# Seperation_Switches.net
KiCad netlist of a schematic drawn in Altium Designer
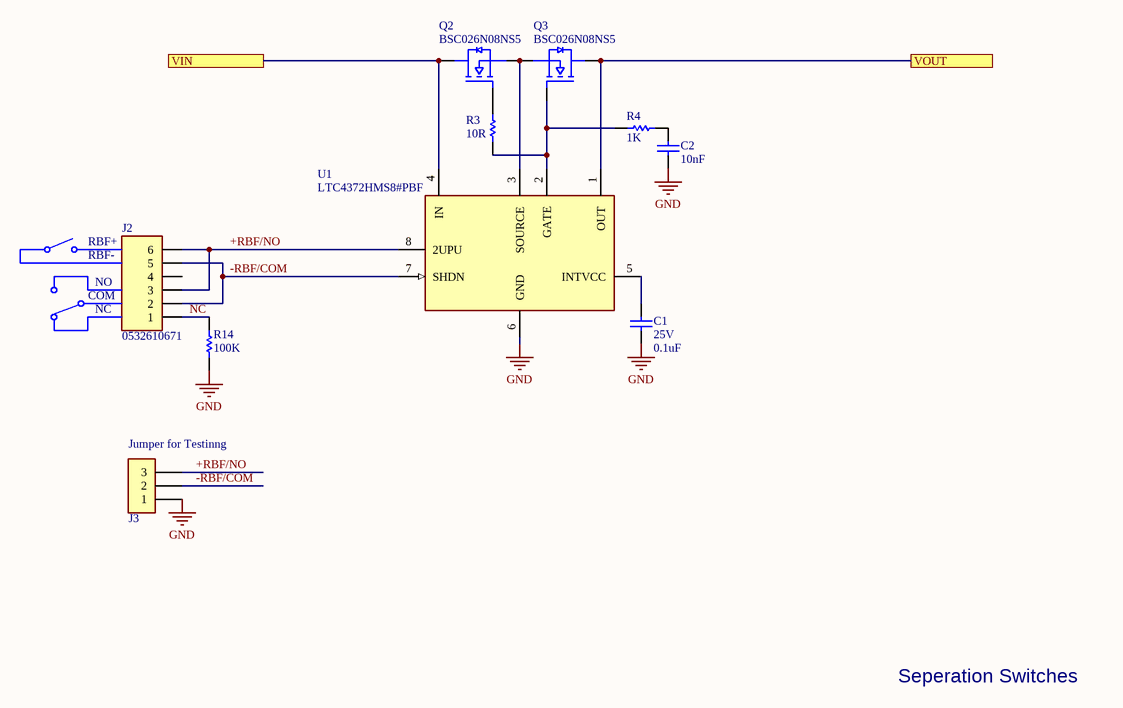
[diagram p0: Seperation_Switches.SchDoc]

(export (version "E")
  (design (tool "Eeschema 10.0.6"))
  (components
    (comp (ref "C1")
      (value "CL21B104KACNNNC")
      (footprint "CAPC0805X060")
      (description "0.1uF ±10% 25V Ceramic Capacitor X7R 0805 (2012 Metric)")
      (fields
        (field (name "DISTRIBUTOR PART NUMBER") "1276-1099-1-ND")
        (field (name "TOLERANCE") "10%")
        (field (name "VOLTAGE RATING") "25V")
        (field (name "CAPACITANCE") "0.1uF")
      )
      (libsource (lib "Ahristi_Library") (part "CL21B104KACNNNC"))
    )
    (comp (ref "C2")
      (value "CL21B103KBANNNC")
      (footprint "CAPC0805X060")
      (description "10nF ±10% 50V Ceramic Capacitor X7R 0805 (2012 Metric)")
      (fields
        (field (name "DISTRIBUTOR PART NUMBER") "1276-1015-1-ND")
        (field (name "TOLERANCE") "10%")
        (field (name "CAPACITANCE") "10nF")
      )
      (libsource (lib "Ahristi_Library") (part "CL21B103KBANNNC"))
    )
    (comp (ref "J2")
      (value "0532610671")
      (footprint "0532610671")
      (description "Connector Header Surface Mount, Right Angle 6 position 0.049\" (1.25mm) Picoblade")
      (fields (field (name "DISTRIBUTOR PART NUMBER") "WM7624CT-ND"))
      (libsource (lib "Ahristi_Library") (part "0532610671"))
    )
    (comp (ref "J3")
      (value "61300311121")
      (footprint "61300311121")
      (description "Header 2.54mm, 1x3 Position")
      (fields (field (name "DISTRIBUTOR PART NUMBER") "732-5316-ND"))
      (libsource (lib "Ahristi_Library") (part "61300311121"))
    )
    (comp (ref "Q2")
      (value "BSC026N08NS5")
      (footprint "PG-TDSON-8-5")
      (description "80V N-Channel 23A (Ta), 100A (Tc) 2.5W (Ta), 156W (Tc) Surface Mount PG-TDSON-8-6")
      (fields (field (name "DISTRIBUTOR PART NUMBER") "BSC026N08NS5ATMA1CT-ND"))
      (libsource (lib "Ahristi_Library") (part "BSC026N08NS5"))
    )
    (comp (ref "Q3")
      (value "BSC026N08NS5")
      (footprint "PG-TDSON-8-5")
      (description "80V N-Channel 23A (Ta), 100A (Tc) 2.5W (Ta), 156W (Tc) Surface Mount PG-TDSON-8-6")
      (fields (field (name "DISTRIBUTOR PART NUMBER") "BSC026N08NS5ATMA1CT-ND"))
      (libsource (lib "Ahristi_Library") (part "BSC026N08NS5"))
    )
    (comp (ref "R3")
      (value "RMCF0603FT10R0")
      (footprint "RESC0603")
      (description "10 Ohms ±1% 0.1W, 1/10W Chip Resistor 0603 (1608 Metric) Automotive AEC-Q200 Thick Film")
      (fields
        (field (name "TOLERANCE") "1%")
        (field (name "DISTRIBUTOR PART NUMBER") "RMCF0603FT10R0CT-ND")
        (field (name "RESISTANCE") "10R")
      )
      (libsource (lib "Ahristi_Library") (part "RMCF0603FT10R0"))
    )
    (comp (ref "R4")
      (value "RNCP0805FTD1K00")
      (footprint "RESC0805")
      (description "1 kOhms ±1% 0.25W, 1/4W Chip Resistor 0805 (2012 Metric) Anti-Sulfur Thin Film")
      (fields
        (field (name "TOLERANCE") "1%")
        (field (name "DISTRIBUTOR PART NUMBER") "RNCP0805FTD1K00CT-ND")
        (field (name "RESISTANCE") "1K")
      )
      (libsource (lib "Ahristi_Library") (part "RNCP0805FTD1K00"))
    )
    (comp (ref "R14")
      (value "RMCF0603FT100K")
      (footprint "RESC0603")
      (description "100 kOhms ±1% 0.1W, 1/10W Chip Resistor 0603 (1608 Metric) Automotive AEC-Q200 Thick Film")
      (fields
        (field (name "TOLERANCE") "1%")
        (field (name "DISTRIBUTOR PART NUMBER") "RMCF0603FT100KCT-ND")
        (field (name "RESISTANCE") "100K")
      )
      (libsource (lib "Ahristi_Library") (part "RMCF0603FT100K"))
    )
    (comp (ref "U1")
      (value "LTC4372HMS8#PBF")
      (footprint "MS8-8LEAD")
      (description "Ideal Diode Controller, 8-lead MSOP SHDN")
      (fields
        (field (name "DISTRIBUTOR PART NUMBER") "505-LTC4372HMS8#PBF-ND")
        (field (name "MANUFACTURER PART NUMBER") "LTC4373CMS8#PBF")
      )
      (libsource (lib "Ahristi_Library") (part "LTC4372HMS8#PBF"))
    )
  )
  (nets
    (net (code "1") (name "/+RBF{slash}NO") (class "Default")
      (node (ref "J2") (pin "3") (pinfunction "3_3") (pintype "passive"))
      (node (ref "J2") (pin "6") (pinfunction "6_6") (pintype "passive"))
      (node (ref "J3") (pin "3") (pinfunction "3_3") (pintype "passive"))
      (node (ref "U1") (pin "8") (pinfunction "2UPU_8") (pintype "passive"))
    )
    (net (code "2") (name "/-RBF{slash}COM") (class "Default")
      (node (ref "J2") (pin "2") (pinfunction "2_2") (pintype "passive"))
      (node (ref "J2") (pin "5") (pinfunction "5_5") (pintype "passive"))
      (node (ref "J3") (pin "2") (pinfunction "2_2") (pintype "passive"))
      (node (ref "U1") (pin "7") (pinfunction "SHDN_7") (pintype "input"))
    )
    (net (code "3") (name "/NC") (class "Default")
      (node (ref "J2") (pin "1") (pinfunction "1_1") (pintype "passive"))
      (node (ref "R14") (pin "2") (pinfunction "2_2") (pintype "passive"))
    )
    (net (code "4") (name "/VIN") (class "Default")
      (node (ref "Q2") (pin "D") (pinfunction "D_D") (pintype "passive"))
      (node (ref "U1") (pin "4") (pinfunction "IN_4") (pintype "passive"))
    )
    (net (code "5") (name "/VOUT") (class "Default")
      (node (ref "Q3") (pin "D") (pinfunction "D_D") (pintype "passive"))
      (node (ref "U1") (pin "1") (pinfunction "OUT_1") (pintype "passive"))
    )
    (net (code "6") (name "GND") (class "Default")
      (node (ref "C1") (pin "1") (pinfunction "1_1") (pintype "passive"))
      (node (ref "C2") (pin "1") (pinfunction "1_1") (pintype "passive"))
      (node (ref "J3") (pin "1") (pinfunction "1_1") (pintype "passive"))
      (node (ref "R14") (pin "1") (pinfunction "1_1") (pintype "passive"))
      (node (ref "U1") (pin "6") (pinfunction "GND_6") (pintype "passive"))
    )
    (net (code "7") (name "Net-(C2-Pad2)") (class "Default")
      (node (ref "C2") (pin "2") (pinfunction "2_2") (pintype "passive"))
      (node (ref "R4") (pin "1") (pinfunction "1_1") (pintype "passive"))
    )
    (net (code "8") (name "Net-(Q2-PadG)") (class "Default")
      (node (ref "Q2") (pin "G") (pinfunction "G_G") (pintype "passive"))
      (node (ref "R3") (pin "2") (pinfunction "2_2") (pintype "passive"))
    )
    (net (code "9") (name "Net-(U1-GATE)") (class "Default")
      (node (ref "Q3") (pin "G") (pinfunction "G_G") (pintype "passive"))
      (node (ref "R3") (pin "1") (pinfunction "1_1") (pintype "passive"))
      (node (ref "R4") (pin "2") (pinfunction "2_2") (pintype "passive"))
      (node (ref "U1") (pin "2") (pinfunction "GATE_2") (pintype "passive"))
    )
    (net (code "10") (name "Net-(U1-INTVCC)") (class "Default")
      (node (ref "C1") (pin "2") (pinfunction "2_2") (pintype "passive"))
      (node (ref "U1") (pin "5") (pinfunction "INTVCC_5") (pintype "passive"))
    )
    (net (code "11") (name "Net-(U1-SOURCE)") (class "Default")
      (node (ref "Q2") (pin "S") (pinfunction "S_S") (pintype "passive"))
      (node (ref "Q3") (pin "S") (pinfunction "S_S") (pintype "passive"))
      (node (ref "U1") (pin "3") (pinfunction "SOURCE_3") (pintype "passive"))
    )
    (net (code "12") (name "unconnected-(J2-Pad4)") (class "Default")
      (node (ref "J2") (pin "4") (pinfunction "4_4") (pintype "passive"))
    )
  )
)
